# RaspiRobot_Board.net
KiCad netlist of a schematic drawn in EAGLE
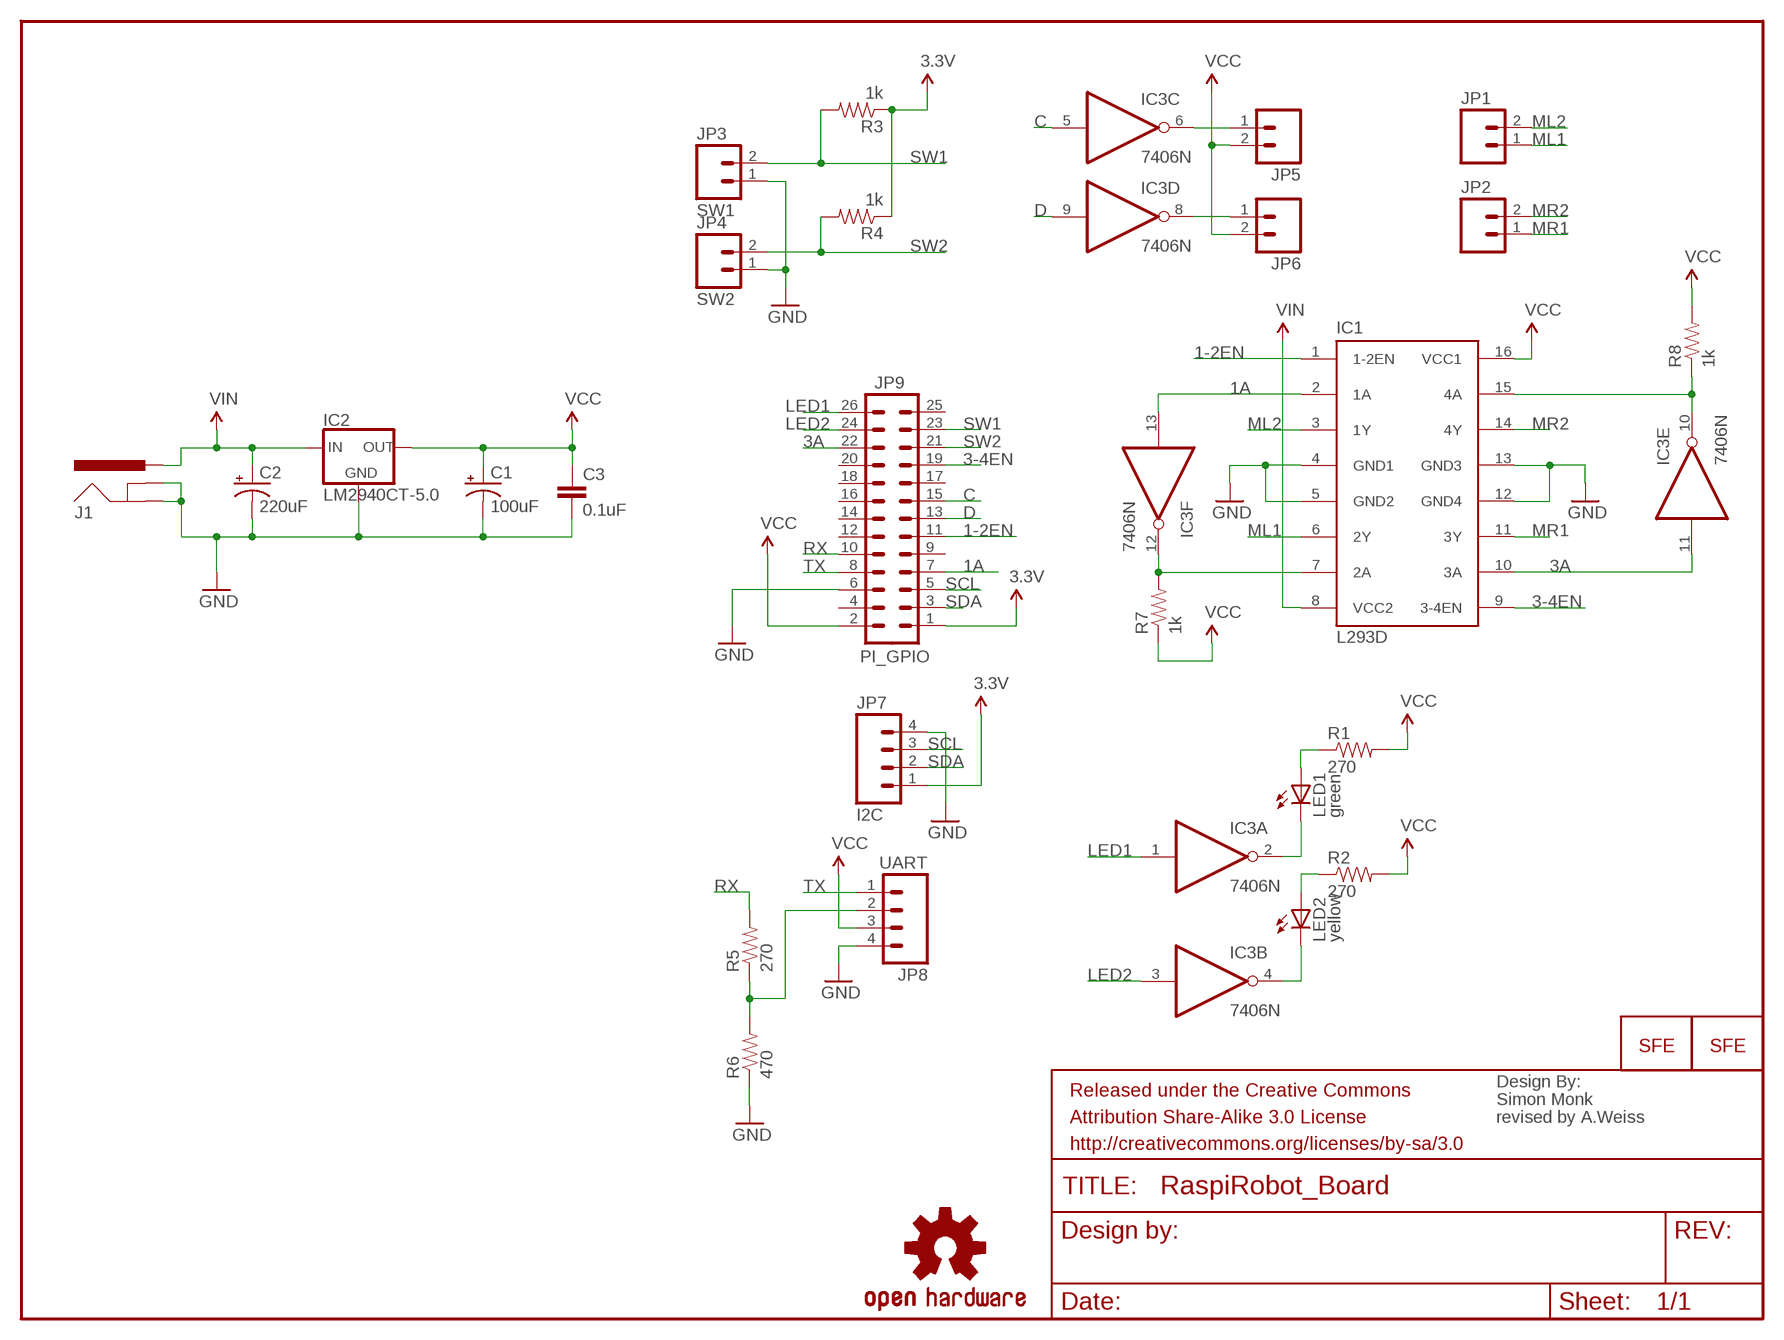
[diagram p0: schematic, sheet 1]

(export (version "E")
  (design (tool "Eeschema 10.0.6"))
  (components
    (comp (ref "C1")
      (value "100uF")
      (footprint "eagle-import:CPOL-RADIAL-100UF-25V")
      (libsource (lib "eagle-import") (part "CAP_POLPTH1"))
    )
    (comp (ref "C2")
      (value "220uF")
      (footprint "eagle-import:CPOL-RADIAL-100UF-25V")
      (libsource (lib "eagle-import") (part "SparkFun-Capacitors_CAP_POLPTH1"))
    )
    (comp (ref "C3")
      (value "0.1uF")
      (footprint "eagle-import:CAP-PTH-SMALL-KIT")
      (libsource (lib "eagle-import") (part "CAPKIT"))
    )
    (comp (ref "FRAME1")
      (value "FRAME-LETTER")
      (footprint "eagle-import:CREATIVE_COMMONS")
      (libsource (lib "eagle-import") (part "FRAME-LETTER"))
    )
    (comp (ref "IC1")
      (value "L293D")
      (footprint "eagle-import:DIL16")
      (libsource (lib "eagle-import") (part "L293D"))
    )
    (comp (ref "IC2")
      (value "LM2940CT-5.0")
      (footprint "eagle-import:TO220-IGO")
      (libsource (lib "eagle-import") (part "V_REG_78XXSINK"))
    )
    (comp (ref "IC3")
      (value "7406N")
      (footprint "eagle-import:DIL14")
      (libsource (lib "eagle-import") (part "7406N"))
    )
    (comp (ref "J1")
      (value "POWER_JACKPTH_LOCK")
      (footprint "eagle-import:POWER_JACK_PTH_LOCK")
      (libsource (lib "eagle-import") (part "POWER_JACKPTH_LOCK"))
    )
    (comp (ref "JP1")
      (value "M023.5MM_LOCK")
      (footprint "eagle-import:SCREWTERMINAL-3.5MM-2_LOCK")
      (libsource (lib "eagle-import") (part "M023.5MM_LOCK"))
    )
    (comp (ref "JP2")
      (value "M023.5MM_LOCK")
      (footprint "eagle-import:SCREWTERMINAL-3.5MM-2_LOCK")
      (libsource (lib "eagle-import") (part "M023.5MM_LOCK"))
    )
    (comp (ref "JP3")
      (value "SW1")
      (footprint "eagle-import:1X02")
      (libsource (lib "eagle-import") (part "M02PTH"))
    )
    (comp (ref "JP4")
      (value "SW2")
      (footprint "eagle-import:1X02")
      (libsource (lib "eagle-import") (part "M02PTH"))
    )
    (comp (ref "JP5")
      (value "M02PTH")
      (footprint "eagle-import:1X02")
      (libsource (lib "eagle-import") (part "M02PTH"))
    )
    (comp (ref "JP6")
      (value "M02PTH")
      (footprint "eagle-import:1X02")
      (libsource (lib "eagle-import") (part "M02PTH"))
    )
    (comp (ref "JP7")
      (value "I2C")
      (footprint "eagle-import:1X04")
      (libsource (lib "eagle-import") (part "M04PTH"))
    )
    (comp (ref "JP8")
      (value "UART")
      (footprint "eagle-import:1X04")
      (libsource (lib "eagle-import") (part "M04PTH"))
    )
    (comp (ref "JP9")
      (value "M13X22X13")
      (footprint "eagle-import:2X13")
      (libsource (lib "eagle-import") (part "M13X22X13"))
    )
    (comp (ref "JP10")
      (value "LOGO-SFENEW")
      (footprint "eagle-import:SFE-NEW-WEBLOGO")
      (libsource (lib "eagle-import") (part "LOGO-SFENEW"))
    )
    (comp (ref "JP11")
      (value "LOGO-SFENEW")
      (footprint "eagle-import:SFE-NEW-WEBLOGO")
      (libsource (lib "eagle-import") (part "LOGO-SFENEW"))
    )
    (comp (ref "LED1")
      (value "green")
      (footprint "eagle-import:LED3MM")
      (libsource (lib "eagle-import") (part "LED3MM"))
    )
    (comp (ref "LED2")
      (value "yellow")
      (footprint "eagle-import:LED3MM")
      (libsource (lib "eagle-import") (part "LED3MM"))
    )
    (comp (ref "R1")
      (value "270")
      (footprint "eagle-import:AXIAL-0.3EZ")
      (libsource (lib "eagle-import") (part "RESISTOREZ"))
    )
    (comp (ref "R2")
      (value "270")
      (footprint "eagle-import:AXIAL-0.3EZ")
      (libsource (lib "eagle-import") (part "RESISTOREZ"))
    )
    (comp (ref "R3")
      (value "1k")
      (footprint "eagle-import:AXIAL-0.3EZ")
      (libsource (lib "eagle-import") (part "RESISTOREZ"))
    )
    (comp (ref "R4")
      (value "1k")
      (footprint "eagle-import:AXIAL-0.3EZ")
      (libsource (lib "eagle-import") (part "RESISTOREZ"))
    )
    (comp (ref "R5")
      (value "270")
      (footprint "eagle-import:AXIAL-0.3EZ")
      (libsource (lib "eagle-import") (part "RESISTOREZ"))
    )
    (comp (ref "R6")
      (value "470")
      (footprint "eagle-import:AXIAL-0.3EZ")
      (libsource (lib "eagle-import") (part "RESISTOREZ"))
    )
    (comp (ref "R7")
      (value "1k")
      (footprint "eagle-import:AXIAL-0.3EZ")
      (libsource (lib "eagle-import") (part "RESISTOREZ"))
    )
    (comp (ref "R8")
      (value "1k")
      (footprint "eagle-import:AXIAL-0.3EZ")
      (libsource (lib "eagle-import") (part "RESISTOREZ"))
    )
    (comp (ref "U$4")
      (value "OSHW-LOGOS")
      (footprint "eagle-import:OSHW-LOGO-S")
      (libsource (lib "eagle-import") (part "OSHW-LOGOS"))
    )
  )
  (nets
    (net (code "1") (name "/1-2EN") (class "Default")
      (node (ref "IC1") (pin "1") (pinfunction "1-2EN_1") (pintype "input"))
      (node (ref "JP9") (pin "11") (pinfunction "11_11") (pintype "passive"))
    )
    (net (code "2") (name "/1A") (class "Default")
      (node (ref "IC1") (pin "2") (pinfunction "1A_2") (pintype "input"))
      (node (ref "IC3") (pin "13") (pinfunction "I_13") (pintype "input"))
      (node (ref "JP9") (pin "7") (pinfunction "7_7") (pintype "passive"))
    )
    (net (code "3") (name "/3-4EN") (class "Default")
      (node (ref "IC1") (pin "9") (pinfunction "3-4EN_9") (pintype "input"))
      (node (ref "JP9") (pin "19") (pinfunction "19_19") (pintype "passive"))
    )
    (net (code "4") (name "/3A") (class "Default")
      (node (ref "IC1") (pin "10") (pinfunction "3A_10") (pintype "input"))
      (node (ref "IC3") (pin "11") (pinfunction "I_11") (pintype "input"))
      (node (ref "JP9") (pin "22") (pinfunction "22_22") (pintype "passive"))
    )
    (net (code "5") (name "/C") (class "Default")
      (node (ref "IC3") (pin "5") (pinfunction "I_5") (pintype "input"))
      (node (ref "JP9") (pin "15") (pinfunction "15_15") (pintype "passive"))
    )
    (net (code "6") (name "/D") (class "Default")
      (node (ref "IC3") (pin "9") (pinfunction "I_9") (pintype "input"))
      (node (ref "JP9") (pin "13") (pinfunction "13_13") (pintype "passive"))
    )
    (net (code "7") (name "/LED1") (class "Default")
      (node (ref "IC3") (pin "1") (pinfunction "I_1") (pintype "input"))
      (node (ref "JP9") (pin "26") (pinfunction "26_26") (pintype "passive"))
    )
    (net (code "8") (name "/LED2") (class "Default")
      (node (ref "IC3") (pin "3") (pinfunction "I_3") (pintype "input"))
      (node (ref "JP9") (pin "24") (pinfunction "24_24") (pintype "passive"))
    )
    (net (code "9") (name "/ML1") (class "Default")
      (node (ref "IC1") (pin "6") (pinfunction "2Y_6") (pintype "output"))
      (node (ref "JP1") (pin "1") (pinfunction "1_1") (pintype "passive"))
    )
    (net (code "10") (name "/ML2") (class "Default")
      (node (ref "IC1") (pin "3") (pinfunction "1Y_3") (pintype "output"))
      (node (ref "JP1") (pin "2") (pinfunction "2_2") (pintype "passive"))
    )
    (net (code "11") (name "/MR1") (class "Default")
      (node (ref "IC1") (pin "11") (pinfunction "3Y_11") (pintype "output"))
      (node (ref "JP2") (pin "1") (pinfunction "1_1") (pintype "passive"))
    )
    (net (code "12") (name "/MR2") (class "Default")
      (node (ref "IC1") (pin "14") (pinfunction "4Y_14") (pintype "output"))
      (node (ref "JP2") (pin "2") (pinfunction "2_2") (pintype "passive"))
    )
    (net (code "13") (name "/RX") (class "Default")
      (node (ref "JP9") (pin "10") (pinfunction "10_10") (pintype "passive"))
      (node (ref "R5") (pin "P$2") (pinfunction "2_P$2") (pintype "passive"))
    )
    (net (code "14") (name "/SCL") (class "Default")
      (node (ref "JP7") (pin "3") (pinfunction "3_3") (pintype "passive"))
      (node (ref "JP9") (pin "5") (pinfunction "5_5") (pintype "passive"))
    )
    (net (code "15") (name "/SDA") (class "Default")
      (node (ref "JP7") (pin "2") (pinfunction "2_2") (pintype "passive"))
      (node (ref "JP9") (pin "3") (pinfunction "3_3") (pintype "passive"))
    )
    (net (code "16") (name "/SW1") (class "Default")
      (node (ref "JP3") (pin "2") (pinfunction "2_2") (pintype "passive"))
      (node (ref "JP9") (pin "23") (pinfunction "23_23") (pintype "passive"))
      (node (ref "R3") (pin "P$2") (pinfunction "2_P$2") (pintype "passive"))
    )
    (net (code "17") (name "/SW2") (class "Default")
      (node (ref "JP4") (pin "2") (pinfunction "2_2") (pintype "passive"))
      (node (ref "JP9") (pin "21") (pinfunction "21_21") (pintype "passive"))
      (node (ref "R4") (pin "P$2") (pinfunction "2_P$2") (pintype "passive"))
    )
    (net (code "18") (name "/TX") (class "Default")
      (node (ref "JP8") (pin "1") (pinfunction "1_1") (pintype "passive"))
      (node (ref "JP9") (pin "8") (pinfunction "8_8") (pintype "passive"))
    )
    (net (code "19") (name "3.3V") (class "Default")
      (node (ref "JP7") (pin "1") (pinfunction "1_1") (pintype "passive"))
      (node (ref "JP9") (pin "1") (pinfunction "1_1") (pintype "passive"))
      (node (ref "R3") (pin "P$1") (pinfunction "1_P$1") (pintype "passive"))
      (node (ref "R4") (pin "P$1") (pinfunction "1_P$1") (pintype "passive"))
    )
    (net (code "20") (name "GND") (class "Default")
      (node (ref "C1") (pin "2") (pinfunction "-_2") (pintype "passive"))
      (node (ref "C2") (pin "2") (pinfunction "-_2") (pintype "passive"))
      (node (ref "C3") (pin "2") (pinfunction "2_2") (pintype "passive"))
      (node (ref "IC1") (pin "12") (pinfunction "GND4_12") (pintype "power_in"))
      (node (ref "IC1") (pin "13") (pinfunction "GND3_13") (pintype "power_in"))
      (node (ref "IC1") (pin "4") (pinfunction "GND1_4") (pintype "power_in"))
      (node (ref "IC1") (pin "5") (pinfunction "GND2_5") (pintype "power_in"))
      (node (ref "IC2") (pin "GND") (pinfunction "GND_GND") (pintype "input"))
      (node (ref "J1") (pin "GND") (pinfunction "GND_GND") (pintype "bidirectional"))
      (node (ref "J1") (pin "GNDBREAK") (pinfunction "GNDBREAK_GNDBREAK") (pintype "bidirectional"))
      (node (ref "JP3") (pin "1") (pinfunction "1_1") (pintype "passive"))
      (node (ref "JP4") (pin "1") (pinfunction "1_1") (pintype "passive"))
      (node (ref "JP7") (pin "4") (pinfunction "4_4") (pintype "passive"))
      (node (ref "JP8") (pin "4") (pinfunction "4_4") (pintype "passive"))
      (node (ref "JP9") (pin "6") (pinfunction "6_6") (pintype "passive"))
      (node (ref "R6") (pin "P$1") (pinfunction "1_P$1") (pintype "passive"))
    )
    (net (code "21") (name "Net-(IC1-2A)") (class "Default")
      (node (ref "IC1") (pin "7") (pinfunction "2A_7") (pintype "input"))
      (node (ref "IC3") (pin "12") (pinfunction "O_12") (pintype "open_collector"))
      (node (ref "R7") (pin "P$2") (pinfunction "2_P$2") (pintype "passive"))
    )
    (net (code "22") (name "Net-(IC1-4A)") (class "Default")
      (node (ref "IC1") (pin "15") (pinfunction "4A_15") (pintype "input"))
      (node (ref "IC3") (pin "10") (pinfunction "O_10") (pintype "open_collector"))
      (node (ref "R8") (pin "P$1") (pinfunction "1_P$1") (pintype "passive"))
    )
    (net (code "23") (name "Net-(IC3A-O)") (class "Default")
      (node (ref "IC3") (pin "2") (pinfunction "O_2") (pintype "open_collector"))
      (node (ref "LED1") (pin "K") (pinfunction "C_K") (pintype "passive"))
    )
    (net (code "24") (name "Net-(IC3B-O)") (class "Default")
      (node (ref "IC3") (pin "4") (pinfunction "O_4") (pintype "open_collector"))
      (node (ref "LED2") (pin "K") (pinfunction "C_K") (pintype "passive"))
    )
    (net (code "25") (name "Net-(IC3C-O)") (class "Default")
      (node (ref "IC3") (pin "6") (pinfunction "O_6") (pintype "open_collector"))
      (node (ref "JP5") (pin "1") (pinfunction "1_1") (pintype "passive"))
    )
    (net (code "26") (name "Net-(IC3D-O)") (class "Default")
      (node (ref "IC3") (pin "8") (pinfunction "O_8") (pintype "open_collector"))
      (node (ref "JP6") (pin "1") (pinfunction "1_1") (pintype "passive"))
    )
    (net (code "27") (name "Net-(R1-1)") (class "Default")
      (node (ref "LED1") (pin "A") (pinfunction "A_A") (pintype "passive"))
      (node (ref "R1") (pin "P$1") (pinfunction "1_P$1") (pintype "passive"))
    )
    (net (code "28") (name "Net-(R2-1)") (class "Default")
      (node (ref "LED2") (pin "A") (pinfunction "A_A") (pintype "passive"))
      (node (ref "R2") (pin "P$1") (pinfunction "1_P$1") (pintype "passive"))
    )
    (net (code "29") (name "Net-(R5-1)") (class "Default")
      (node (ref "JP8") (pin "2") (pinfunction "2_2") (pintype "passive"))
      (node (ref "R5") (pin "P$1") (pinfunction "1_P$1") (pintype "passive"))
      (node (ref "R6") (pin "P$2") (pinfunction "2_P$2") (pintype "passive"))
    )
    (net (code "30") (name "VCC") (class "Default")
      (node (ref "C1") (pin "1") (pinfunction "+_1") (pintype "passive"))
      (node (ref "C3") (pin "1") (pinfunction "1_1") (pintype "passive"))
      (node (ref "IC1") (pin "16") (pinfunction "VCC1_16") (pintype "power_in"))
      (node (ref "IC2") (pin "OUT") (pinfunction "OUT_OUT") (pintype "output"))
      (node (ref "JP5") (pin "2") (pinfunction "2_2") (pintype "passive"))
      (node (ref "JP6") (pin "2") (pinfunction "2_2") (pintype "passive"))
      (node (ref "JP8") (pin "3") (pinfunction "3_3") (pintype "passive"))
      (node (ref "JP9") (pin "2") (pinfunction "2_2") (pintype "passive"))
      (node (ref "R1") (pin "P$2") (pinfunction "2_P$2") (pintype "passive"))
      (node (ref "R2") (pin "P$2") (pinfunction "2_P$2") (pintype "passive"))
      (node (ref "R7") (pin "P$1") (pinfunction "1_P$1") (pintype "passive"))
      (node (ref "R8") (pin "P$2") (pinfunction "2_P$2") (pintype "passive"))
    )
    (net (code "31") (name "VIN") (class "Default")
      (node (ref "C2") (pin "1") (pinfunction "+_1") (pintype "passive"))
      (node (ref "IC1") (pin "8") (pinfunction "VCC2_8") (pintype "power_in"))
      (node (ref "IC2") (pin "IN") (pinfunction "IN_IN") (pintype "input"))
      (node (ref "J1") (pin "PWR") (pinfunction "PWR_PWR") (pintype "bidirectional"))
    )
    (net (code "32") (name "unconnected-(JP9-Pad4)") (class "Default")
      (node (ref "JP9") (pin "4") (pinfunction "4_4") (pintype "passive"))
    )
    (net (code "33") (name "unconnected-(JP9-Pad9)") (class "Default")
      (node (ref "JP9") (pin "9") (pinfunction "9_9") (pintype "passive"))
    )
    (net (code "34") (name "unconnected-(JP9-Pad12)") (class "Default")
      (node (ref "JP9") (pin "12") (pinfunction "12_12") (pintype "passive"))
    )
    (net (code "35") (name "unconnected-(JP9-Pad14)") (class "Default")
      (node (ref "JP9") (pin "14") (pinfunction "14_14") (pintype "passive"))
    )
    (net (code "36") (name "unconnected-(JP9-Pad16)") (class "Default")
      (node (ref "JP9") (pin "16") (pinfunction "16_16") (pintype "passive"))
    )
    (net (code "37") (name "unconnected-(JP9-Pad17)") (class "Default")
      (node (ref "JP9") (pin "17") (pinfunction "17_17") (pintype "passive"))
    )
    (net (code "38") (name "unconnected-(JP9-Pad18)") (class "Default")
      (node (ref "JP9") (pin "18") (pinfunction "18_18") (pintype "passive"))
    )
    (net (code "39") (name "unconnected-(JP9-Pad20)") (class "Default")
      (node (ref "JP9") (pin "20") (pinfunction "20_20") (pintype "passive"))
    )
    (net (code "40") (name "unconnected-(JP9-Pad25)") (class "Default")
      (node (ref "JP9") (pin "25") (pinfunction "25_25") (pintype "passive"))
    )
  )
)
